# YAPM.net
KiCad netlist of a schematic drawn in EAGLE
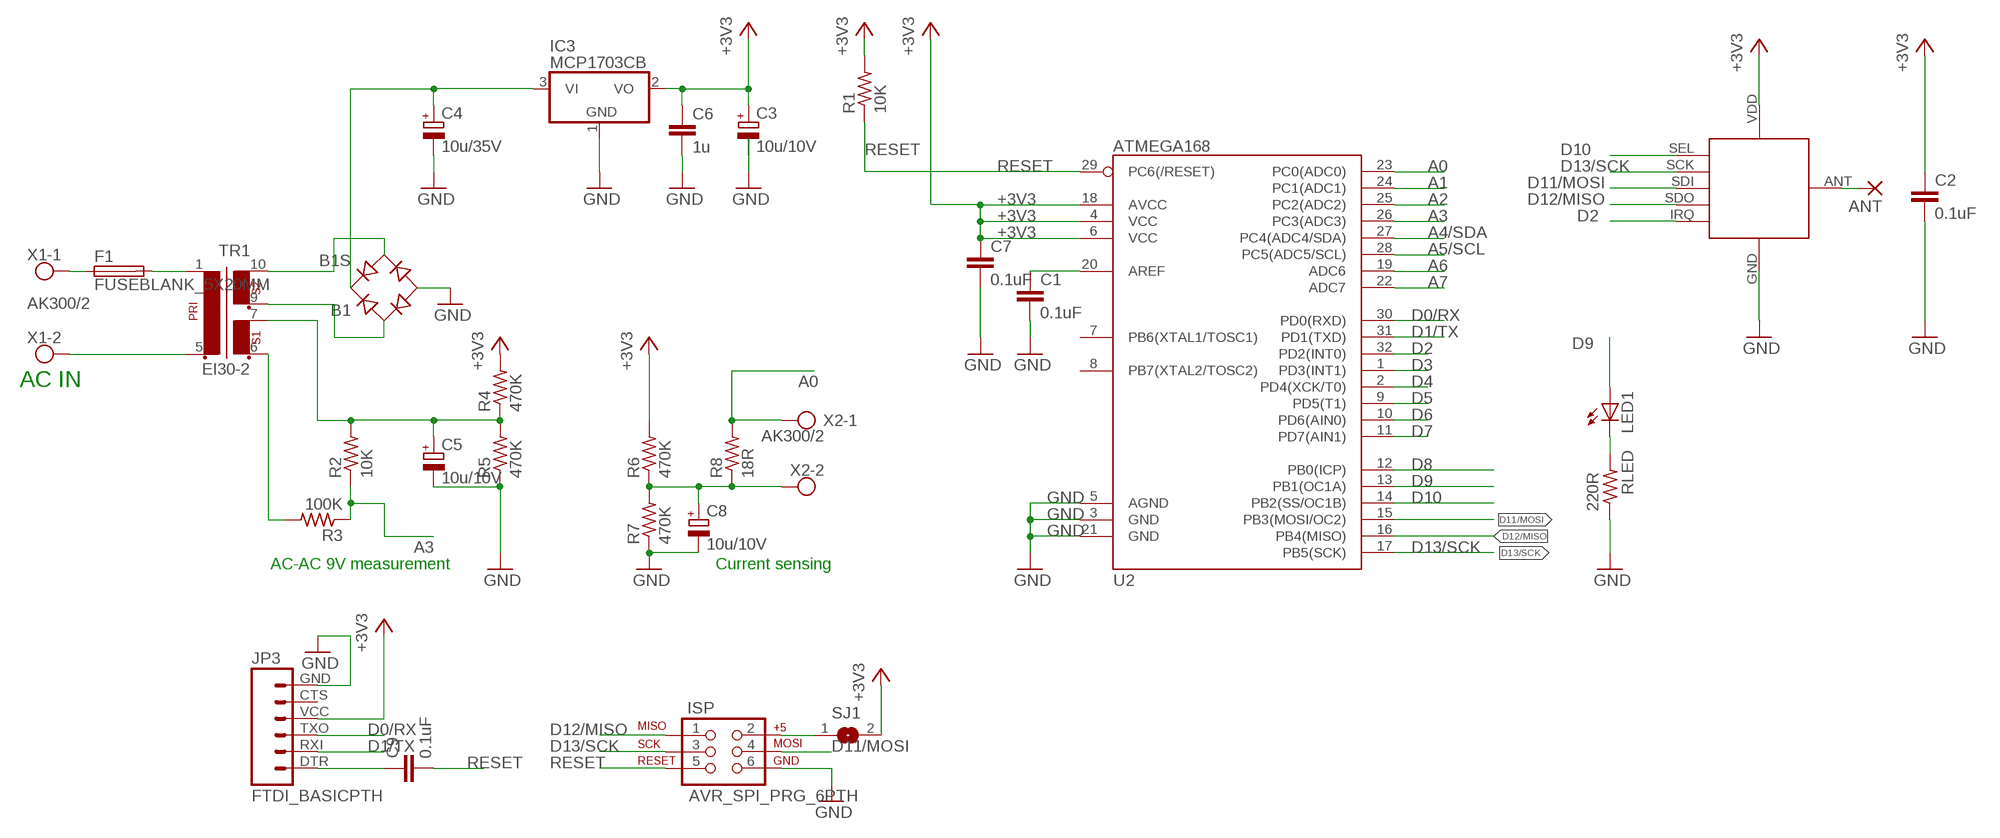
[diagram p0: schematic, sheet 1]

(export (version "E")
  (design (tool "Eeschema 10.0.6"))
  (components
    (comp (ref "ANT")
      (value "1,6/0,8")
      (footprint "eagle-import:1,6_0,8")
      (libsource (lib "eagle-import") (part "1,6/0,8"))
    )
    (comp (ref "B1")
      (value "B1S")
      (footprint "eagle-import:MBS")
      (libsource (lib "eagle-import") (part "BS1"))
    )
    (comp (ref "C1")
      (value "0.1uF")
      (footprint "eagle-import:C0603")
      (libsource (lib "eagle-import") (part "resistor_C-EUC0603"))
    )
    (comp (ref "C2")
      (value "0.1uF")
      (footprint "eagle-import:C0603")
      (libsource (lib "eagle-import") (part "C-EUC0603"))
    )
    (comp (ref "C3")
      (value "10u/10V")
      (footprint "eagle-import:SMC_A")
      (libsource (lib "eagle-import") (part "CPOL-EUSMCA"))
    )
    (comp (ref "C4")
      (value "10u/35V")
      (footprint "eagle-import:SMC_C")
      (libsource (lib "eagle-import") (part "CPOL-EUSMCC"))
    )
    (comp (ref "C5")
      (value "10u/10V")
      (footprint "eagle-import:SMC_A")
      (libsource (lib "eagle-import") (part "CPOL-EUSMCA"))
    )
    (comp (ref "C6")
      (value "1u")
      (footprint "eagle-import:C0603K")
      (libsource (lib "eagle-import") (part "C-EUC0603K"))
    )
    (comp (ref "C7")
      (value "0.1uF")
      (footprint "eagle-import:C0603")
      (libsource (lib "eagle-import") (part "resistor_C-EUC0603"))
    )
    (comp (ref "C8")
      (value "10u/10V")
      (footprint "eagle-import:SMC_A")
      (libsource (lib "eagle-import") (part "CPOL-EUSMCA"))
    )
    (comp (ref "C9")
      (value "0.1uF")
      (footprint "eagle-import:C0603")
      (libsource (lib "eagle-import") (part "resistor_C-EUC0603"))
    )
    (comp (ref "F1")
      (value "FUSEBLANK_5X20MM")
      (footprint "eagle-import:FUSE_HOLDER_5X20MM")
      (libsource (lib "eagle-import") (part "FUSEBLANK_5X20MM"))
    )
    (comp (ref "IC3")
      (value "MCP1703CB")
      (footprint "eagle-import:SOT23")
      (libsource (lib "eagle-import") (part "MCP1703CB"))
    )
    (comp (ref "ISP")
      (value "AVR_SPI_PRG_6PTH")
      (footprint "eagle-import:2X3")
      (libsource (lib "eagle-import") (part "AVR_SPI_PRG_6PTH"))
    )
    (comp (ref "JP3")
      (value "FTDI_BASICPTH")
      (footprint "eagle-import:FTDI_BASIC")
      (libsource (lib "eagle-import") (part "FTDI_BASICPTH"))
    )
    (comp (ref "LED1")
      (value "LEDSML0603")
      (footprint "eagle-import:SML0603")
      (libsource (lib "eagle-import") (part "LEDSML0603"))
    )
    (comp (ref "R1")
      (value "10K")
      (footprint "eagle-import:R0603")
      (libsource (lib "eagle-import") (part "R-US_R0603"))
    )
    (comp (ref "R2")
      (value "10K")
      (footprint "eagle-import:R0603")
      (libsource (lib "eagle-import") (part "R-US_R0603"))
    )
    (comp (ref "R3")
      (value "100K")
      (footprint "eagle-import:R0603")
      (libsource (lib "eagle-import") (part "R-US_R0603"))
    )
    (comp (ref "R4")
      (value "470K")
      (footprint "eagle-import:R0603")
      (libsource (lib "eagle-import") (part "R-US_R0603"))
    )
    (comp (ref "R5")
      (value "470K")
      (footprint "eagle-import:R0603")
      (libsource (lib "eagle-import") (part "R-US_R0603"))
    )
    (comp (ref "R6")
      (value "470K")
      (footprint "eagle-import:R0603")
      (libsource (lib "eagle-import") (part "R-US_R0603"))
    )
    (comp (ref "R7")
      (value "470K")
      (footprint "eagle-import:R0603")
      (libsource (lib "eagle-import") (part "R-US_R0603"))
    )
    (comp (ref "R8")
      (value "18R")
      (footprint "eagle-import:R0603")
      (libsource (lib "eagle-import") (part "R-US_R0603"))
    )
    (comp (ref "RFM12B1")
      (value "RFM12B_MINPADS")
      (footprint "eagle-import:RFM12B-MINPADS")
      (libsource (lib "eagle-import") (part "RFM12B_MINPADS"))
    )
    (comp (ref "RLED")
      (value "220R")
      (footprint "eagle-import:R0603")
      (libsource (lib "eagle-import") (part "R-US_R0603"))
    )
    (comp (ref "SJ1") (value "SJ") (footprint "eagle-import:SJ") (libsource (lib "eagle-import") (part "SJ")))
    (comp (ref "TR1")
      (value "EI30-2")
      (footprint "eagle-import:EI30-2")
      (libsource (lib "eagle-import") (part "EI30-2"))
    )
    (comp (ref "U2")
      (value "ATMEGA168")
      (footprint "eagle-import:TQFP32-08")
      (libsource (lib "eagle-import") (part "ATMEGA168"))
    )
    (comp (ref "X1")
      (value "AK300/2")
      (footprint "eagle-import:AK300_2")
      (libsource (lib "eagle-import") (part "AK300/2"))
    )
    (comp (ref "X2")
      (value "AK300/2")
      (footprint "eagle-import:AK300_2")
      (fields (field (name "OC_FARNELL") "unknown") (field (name "OC_NEWARK") "unknown"))
      (libsource (lib "eagle-import") (part "AK300/2"))
    )
  )
  (nets
    (net (code "1") (name "+3V3") (class "Default")
      (node (ref "C2") (pin "1") (pinfunction "1_1") (pintype "passive"))
      (node (ref "C3") (pin "+") (pinfunction "+_+") (pintype "passive"))
      (node (ref "C6") (pin "1") (pinfunction "1_1") (pintype "passive"))
      (node (ref "C7") (pin "1") (pinfunction "1_1") (pintype "passive"))
      (node (ref "IC3") (pin "2") (pinfunction "VO_2") (pintype "passive"))
      (node (ref "JP3") (pin "VCC") (pinfunction "4_VCC") (pintype "passive"))
      (node (ref "R1") (pin "2") (pinfunction "2_2") (pintype "passive"))
      (node (ref "R4") (pin "2") (pinfunction "2_2") (pintype "passive"))
      (node (ref "R6") (pin "2") (pinfunction "2_2") (pintype "passive"))
      (node (ref "RFM12B1") (pin "VDD") (pinfunction "VDD_VDD") (pintype "bidirectional"))
      (node (ref "SJ1") (pin "2") (pinfunction "2_2") (pintype "passive"))
      (node (ref "U2") (pin "18") (pinfunction "AVCC_18") (pintype "bidirectional"))
      (node (ref "U2") (pin "4") (pinfunction "VCC_4") (pintype "bidirectional"))
      (node (ref "U2") (pin "6") (pinfunction "VCC_6") (pintype "bidirectional"))
    )
    (net (code "2") (name "/A0") (class "Default")
      (node (ref "R8") (pin "2") (pinfunction "2_2") (pintype "passive"))
      (node (ref "U2") (pin "23") (pinfunction "PC0(ADC0)_23") (pintype "bidirectional"))
      (node (ref "X2") (pin "1") (pinfunction "KL_1") (pintype "passive"))
    )
    (net (code "3") (name "/A1") (class "Default")
      (node (ref "U2") (pin "24") (pinfunction "PC1(ADC1)_24") (pintype "bidirectional"))
    )
    (net (code "4") (name "/A2") (class "Default")
      (node (ref "U2") (pin "25") (pinfunction "PC2(ADC2)_25") (pintype "bidirectional"))
    )
    (net (code "5") (name "/A3") (class "Default")
      (node (ref "R2") (pin "1") (pinfunction "1_1") (pintype "passive"))
      (node (ref "R3") (pin "1") (pinfunction "1_1") (pintype "passive"))
      (node (ref "U2") (pin "26") (pinfunction "PC3(ADC3)_26") (pintype "bidirectional"))
    )
    (net (code "6") (name "/A4{slash}SDA") (class "Default")
      (node (ref "U2") (pin "27") (pinfunction "PC4(ADC4/SDA)_27") (pintype "bidirectional"))
    )
    (net (code "7") (name "/A5{slash}SCL") (class "Default")
      (node (ref "U2") (pin "28") (pinfunction "PC5(ADC5/SCL)_28") (pintype "bidirectional"))
    )
    (net (code "8") (name "/A6") (class "Default")
      (node (ref "U2") (pin "19") (pinfunction "ADC6_19") (pintype "bidirectional"))
    )
    (net (code "9") (name "/A7") (class "Default")
      (node (ref "U2") (pin "22") (pinfunction "ADC7_22") (pintype "bidirectional"))
    )
    (net (code "10") (name "/D0{slash}RX") (class "Default")
      (node (ref "JP3") (pin "TXO") (pinfunction "3_TXO") (pintype "passive"))
      (node (ref "U2") (pin "30") (pinfunction "PD0(RXD)_30") (pintype "bidirectional"))
    )
    (net (code "11") (name "/D1{slash}TX") (class "Default")
      (node (ref "JP3") (pin "RXI") (pinfunction "2_RXI") (pintype "passive"))
      (node (ref "U2") (pin "31") (pinfunction "PD1(TXD)_31") (pintype "bidirectional"))
    )
    (net (code "12") (name "/D2") (class "Default")
      (node (ref "RFM12B1") (pin "IRQ") (pinfunction "IRQ_IRQ") (pintype "bidirectional"))
      (node (ref "U2") (pin "32") (pinfunction "PD2(INT0)_32") (pintype "bidirectional"))
    )
    (net (code "13") (name "/D3") (class "Default")
      (node (ref "U2") (pin "1") (pinfunction "PD3(INT1)_1") (pintype "bidirectional"))
    )
    (net (code "14") (name "/D4") (class "Default")
      (node (ref "U2") (pin "2") (pinfunction "PD4(XCK/T0)_2") (pintype "bidirectional"))
    )
    (net (code "15") (name "/D5") (class "Default")
      (node (ref "U2") (pin "9") (pinfunction "PD5(T1)_9") (pintype "bidirectional"))
    )
    (net (code "16") (name "/D6") (class "Default")
      (node (ref "U2") (pin "10") (pinfunction "PD6(AIN0)_10") (pintype "bidirectional"))
    )
    (net (code "17") (name "/D7") (class "Default")
      (node (ref "U2") (pin "11") (pinfunction "PD7(AIN1)_11") (pintype "bidirectional"))
    )
    (net (code "18") (name "/D8") (class "Default")
      (node (ref "U2") (pin "12") (pinfunction "PB0(ICP)_12") (pintype "bidirectional"))
    )
    (net (code "19") (name "/D9") (class "Default")
      (node (ref "LED1") (pin "A") (pinfunction "A_A") (pintype "passive"))
      (node (ref "U2") (pin "13") (pinfunction "PB1(OC1A)_13") (pintype "bidirectional"))
    )
    (net (code "20") (name "/D10") (class "Default")
      (node (ref "RFM12B1") (pin "SEL") (pinfunction "SEL_SEL") (pintype "bidirectional"))
      (node (ref "U2") (pin "14") (pinfunction "PB2(SS/OC1B)_14") (pintype "bidirectional"))
    )
    (net (code "21") (name "/RESET") (class "Default")
      (node (ref "C9") (pin "2") (pinfunction "2_2") (pintype "passive"))
      (node (ref "ISP") (pin "5") (pinfunction "5_5") (pintype "passive"))
      (node (ref "R1") (pin "1") (pinfunction "1_1") (pintype "passive"))
      (node (ref "U2") (pin "29") (pinfunction "PC6(/RESET)_29") (pintype "bidirectional"))
    )
    (net (code "22") (name "D11{slash}MOSI") (class "Default")
      (node (ref "ISP") (pin "4") (pinfunction "4_4") (pintype "passive"))
      (node (ref "RFM12B1") (pin "SDI") (pinfunction "SDI/MOSI_SDI") (pintype "bidirectional"))
      (node (ref "U2") (pin "15") (pinfunction "PB3(MOSI/OC2)_15") (pintype "bidirectional"))
    )
    (net (code "23") (name "D12{slash}MISO") (class "Default")
      (node (ref "ISP") (pin "1") (pinfunction "1_1") (pintype "passive"))
      (node (ref "RFM12B1") (pin "SDO") (pinfunction "SDO/MISO_SDO") (pintype "bidirectional"))
      (node (ref "U2") (pin "16") (pinfunction "PB4(MISO)_16") (pintype "bidirectional"))
    )
    (net (code "24") (name "D13{slash}SCK") (class "Default")
      (node (ref "ISP") (pin "3") (pinfunction "3_3") (pintype "passive"))
      (node (ref "RFM12B1") (pin "SCK") (pinfunction "SCK_SCK") (pintype "bidirectional"))
      (node (ref "U2") (pin "17") (pinfunction "PB5(SCK)_17") (pintype "bidirectional"))
    )
    (net (code "25") (name "GND") (class "Default")
      (node (ref "B1") (pin "-") (pinfunction "-_-") (pintype "passive"))
      (node (ref "C1") (pin "2") (pinfunction "2_2") (pintype "passive"))
      (node (ref "C2") (pin "2") (pinfunction "2_2") (pintype "passive"))
      (node (ref "C3") (pin "-") (pinfunction "-_-") (pintype "passive"))
      (node (ref "C4") (pin "-") (pinfunction "-_-") (pintype "passive"))
      (node (ref "C5") (pin "-") (pinfunction "-_-") (pintype "passive"))
      (node (ref "C6") (pin "2") (pinfunction "2_2") (pintype "passive"))
      (node (ref "C7") (pin "2") (pinfunction "2_2") (pintype "passive"))
      (node (ref "C8") (pin "-") (pinfunction "-_-") (pintype "passive"))
      (node (ref "IC3") (pin "1") (pinfunction "GND_1") (pintype "passive"))
      (node (ref "ISP") (pin "6") (pinfunction "6_6") (pintype "passive"))
      (node (ref "JP3") (pin "GND") (pinfunction "6_GND") (pintype "passive"))
      (node (ref "R5") (pin "1") (pinfunction "1_1") (pintype "passive"))
      (node (ref "R7") (pin "1") (pinfunction "1_1") (pintype "passive"))
      (node (ref "RFM12B1") (pin "GND") (pinfunction "GND_GND") (pintype "bidirectional"))
      (node (ref "RLED") (pin "1") (pinfunction "1_1") (pintype "passive"))
      (node (ref "U2") (pin "21") (pinfunction "GND_21") (pintype "bidirectional"))
      (node (ref "U2") (pin "3") (pinfunction "GND_3") (pintype "bidirectional"))
      (node (ref "U2") (pin "5") (pinfunction "AGND_5") (pintype "bidirectional"))
    )
    (net (code "26") (name "Net-(ANT-P)") (class "Default")
      (node (ref "ANT") (pin "1") (pinfunction "P_1") (pintype "passive"))
      (node (ref "RFM12B1") (pin "ANT") (pinfunction "ANT_ANT") (pintype "bidirectional"))
    )
    (net (code "27") (name "Net-(F1-Pad2)") (class "Default")
      (node (ref "F1") (pin "2") (pinfunction "2_2") (pintype "passive"))
      (node (ref "TR1") (pin "1") (pinfunction "1_1") (pintype "passive"))
    )
    (net (code "28") (name "Net-(IC3-VI)") (class "Default")
      (node (ref "B1") (pin "+") (pinfunction "+_+") (pintype "passive"))
      (node (ref "C4") (pin "+") (pinfunction "+_+") (pintype "passive"))
      (node (ref "IC3") (pin "3") (pinfunction "VI_3") (pintype "input"))
    )
    (net (code "29") (name "Net-(ISP-Pad2)") (class "Default")
      (node (ref "ISP") (pin "2") (pinfunction "2_2") (pintype "passive"))
      (node (ref "SJ1") (pin "1") (pinfunction "1_1") (pintype "passive"))
    )
    (net (code "30") (name "Net-(JP3-1)") (class "Default")
      (node (ref "C9") (pin "1") (pinfunction "1_1") (pintype "passive"))
      (node (ref "JP3") (pin "DTR") (pinfunction "1_DTR") (pintype "passive"))
    )
    (net (code "31") (name "Net-(LED1-PadC)") (class "Default")
      (node (ref "LED1") (pin "C") (pinfunction "C_C") (pintype "passive"))
      (node (ref "RLED") (pin "2") (pinfunction "2_2") (pintype "passive"))
    )
    (net (code "32") (name "Net-(TR1-2)") (class "Default")
      (node (ref "TR1") (pin "5") (pinfunction "2_5") (pintype "passive"))
      (node (ref "X1") (pin "2") (pinfunction "KL_2") (pintype "passive"))
    )
    (net (code "33") (name "Net-(TR1-3)") (class "Default")
      (node (ref "R3") (pin "2") (pinfunction "2_2") (pintype "passive"))
      (node (ref "TR1") (pin "6") (pinfunction "3_6") (pintype "passive"))
    )
    (net (code "34") (name "Net-(TR1-4)") (class "Default")
      (node (ref "C5") (pin "+") (pinfunction "+_+") (pintype "passive"))
      (node (ref "R2") (pin "2") (pinfunction "2_2") (pintype "passive"))
      (node (ref "R4") (pin "1") (pinfunction "1_1") (pintype "passive"))
      (node (ref "R5") (pin "2") (pinfunction "2_2") (pintype "passive"))
      (node (ref "TR1") (pin "7") (pinfunction "4_7") (pintype "passive"))
    )
    (net (code "35") (name "Net-(TR1-5)") (class "Default")
      (node (ref "B1") (pin "AC1") (pinfunction "AC1_AC1") (pintype "passive"))
      (node (ref "TR1") (pin "9") (pinfunction "5_9") (pintype "passive"))
    )
    (net (code "36") (name "Net-(TR1-6)") (class "Default")
      (node (ref "B1") (pin "AC2") (pinfunction "AC2_AC2") (pintype "passive"))
      (node (ref "TR1") (pin "10") (pinfunction "6_10") (pintype "passive"))
    )
    (net (code "37") (name "Net-(U2-AREF)") (class "Default")
      (node (ref "C1") (pin "1") (pinfunction "1_1") (pintype "passive"))
      (node (ref "U2") (pin "20") (pinfunction "AREF_20") (pintype "bidirectional"))
    )
    (net (code "38") (name "Net-(X1A-KL)") (class "Default")
      (node (ref "F1") (pin "1") (pinfunction "1_1") (pintype "passive"))
      (node (ref "X1") (pin "1") (pinfunction "KL_1") (pintype "passive"))
    )
    (net (code "39") (name "Net-(X2B-KL)") (class "Default")
      (node (ref "C8") (pin "+") (pinfunction "+_+") (pintype "passive"))
      (node (ref "R6") (pin "1") (pinfunction "1_1") (pintype "passive"))
      (node (ref "R7") (pin "2") (pinfunction "2_2") (pintype "passive"))
      (node (ref "R8") (pin "1") (pinfunction "1_1") (pintype "passive"))
      (node (ref "X2") (pin "2") (pinfunction "KL_2") (pintype "passive"))
    )
    (net (code "40") (name "unconnected-(JP3-5-PadCTS)") (class "Default")
      (node (ref "JP3") (pin "CTS") (pinfunction "5_CTS") (pintype "passive"))
    )
    (net (code "41") (name "unconnected-(U2-PB6(XTAL1{slash}TOSC1)-Pad7)") (class "Default")
      (node (ref "U2") (pin "7") (pinfunction "PB6(XTAL1/TOSC1)_7") (pintype "bidirectional"))
    )
    (net (code "42") (name "unconnected-(U2-PB7(XTAL2{slash}TOSC2)-Pad8)") (class "Default")
      (node (ref "U2") (pin "8") (pinfunction "PB7(XTAL2/TOSC2)_8") (pintype "bidirectional"))
    )
  )
)
